# Energy_Sensor.net
KiCad netlist of a schematic drawn in EAGLE
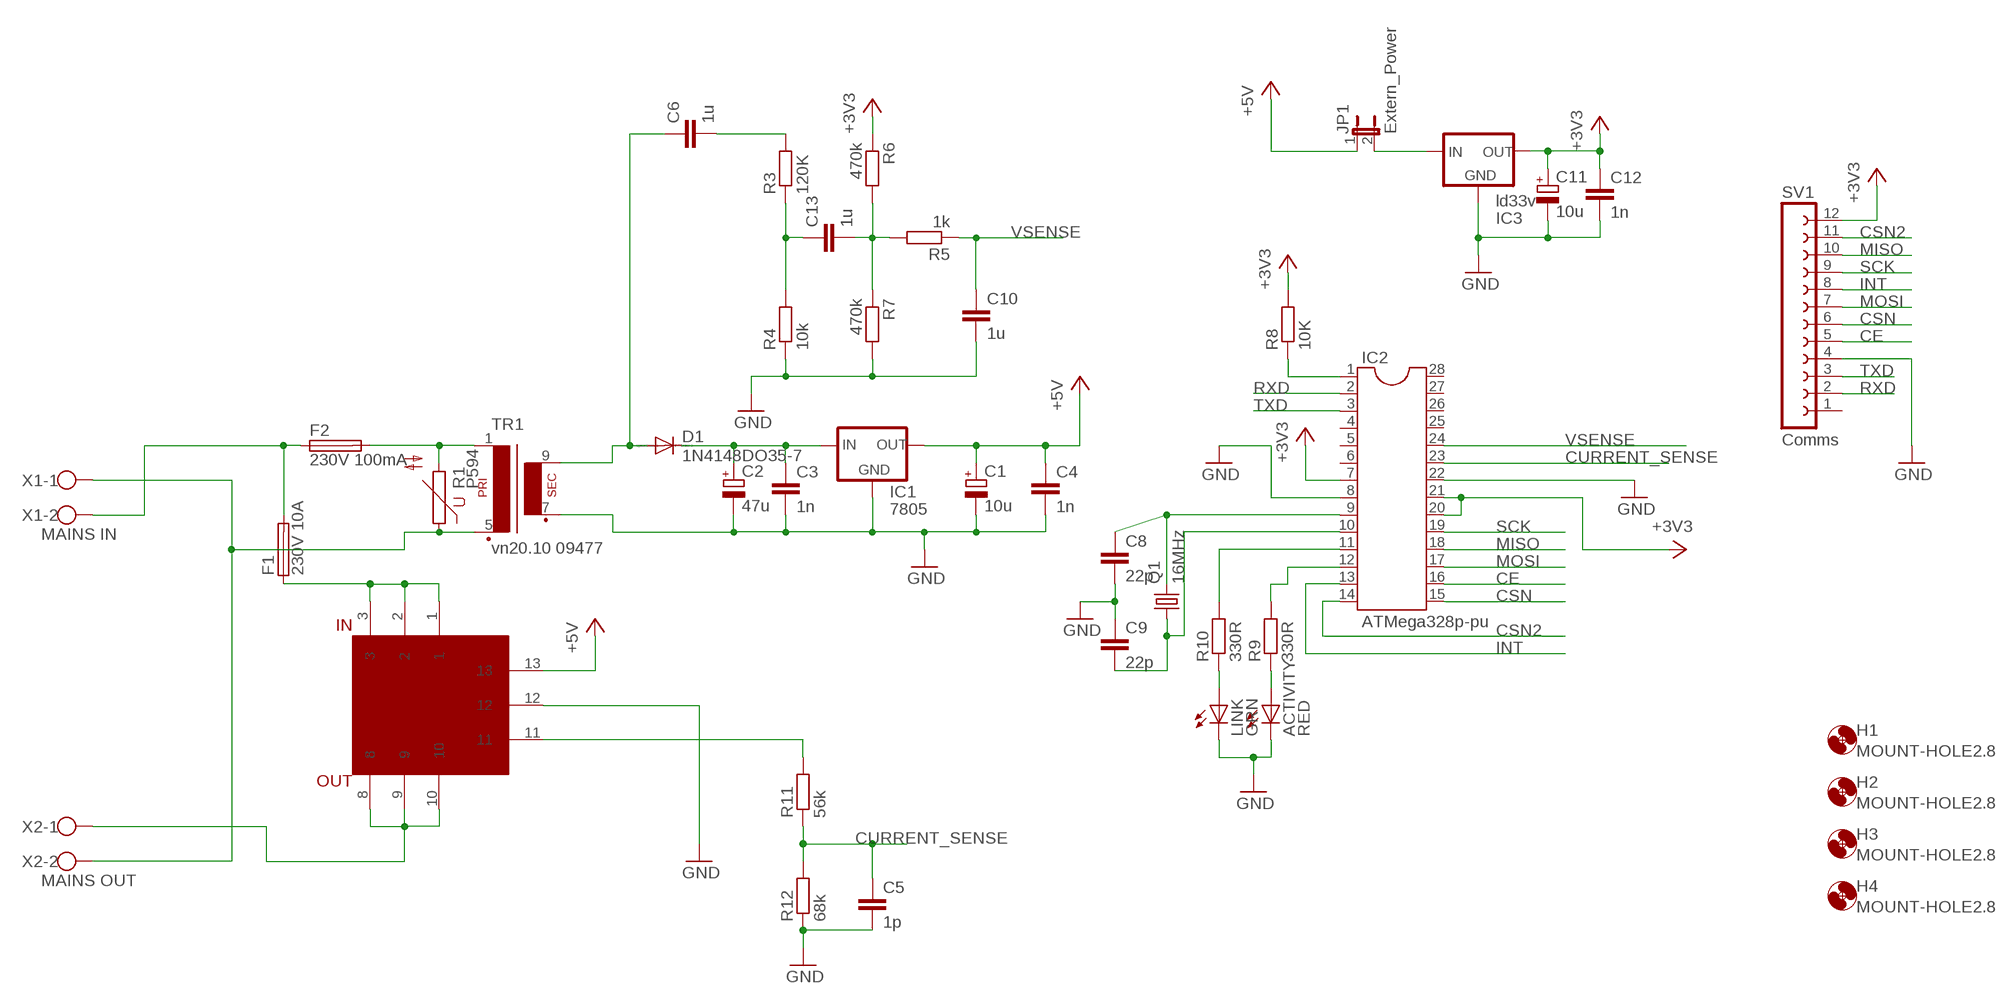
[diagram p0: schematic, sheet 1]

(export (version "E")
  (design (tool "Eeschema 10.0.6"))
  (components
    (comp (ref "ACTIVITY")
      (value "RED")
      (footprint "eagle-import:LED5MM")
      (libsource (lib "eagle-import") (part "LED5MM"))
    )
    (comp (ref "C1")
      (value "10u")
      (footprint "eagle-import:E2,5-6")
      (libsource (lib "eagle-import") (part "CPOL-EUE2.5-6"))
    )
    (comp (ref "C2")
      (value "47u")
      (footprint "eagle-import:E2,5-6")
      (libsource (lib "eagle-import") (part "CPOL-EUE2.5-6"))
    )
    (comp (ref "C3")
      (value "1n")
      (footprint "eagle-import:C025-025X050")
      (libsource (lib "eagle-import") (part "C-EU025-025X050"))
    )
    (comp (ref "C4")
      (value "1n")
      (footprint "eagle-import:C025-025X050")
      (libsource (lib "eagle-import") (part "C-EU025-025X050"))
    )
    (comp (ref "C5")
      (value "1p")
      (footprint "eagle-import:C025-025X050")
      (libsource (lib "eagle-import") (part "C-EU025-025X050"))
    )
    (comp (ref "C6")
      (value "1u")
      (footprint "eagle-import:C025-025X050")
      (libsource (lib "eagle-import") (part "C-EU025-025X050"))
    )
    (comp (ref "C8")
      (value "22p")
      (footprint "eagle-import:C025-025X050")
      (libsource (lib "eagle-import") (part "C-EU025-025X050"))
    )
    (comp (ref "C9")
      (value "22p")
      (footprint "eagle-import:C025-025X050")
      (libsource (lib "eagle-import") (part "C-EU025-025X050"))
    )
    (comp (ref "C10")
      (value "1u")
      (footprint "eagle-import:C025-025X050")
      (libsource (lib "eagle-import") (part "C-EU025-025X050"))
    )
    (comp (ref "C11")
      (value "10u")
      (footprint "eagle-import:E2,5-6")
      (libsource (lib "eagle-import") (part "CPOL-EUE2.5-6"))
    )
    (comp (ref "C12")
      (value "1n")
      (footprint "eagle-import:C025-025X050")
      (libsource (lib "eagle-import") (part "C-EU025-025X050"))
    )
    (comp (ref "C13")
      (value "1u")
      (footprint "eagle-import:C025-025X050")
      (libsource (lib "eagle-import") (part "C-EU025-025X050"))
    )
    (comp (ref "D1")
      (value "1N4148DO35-7")
      (footprint "eagle-import:DO35-7")
      (libsource (lib "eagle-import") (part "1N4148DO35-7"))
    )
    (comp (ref "F1")
      (value "230V 10A")
      (footprint "eagle-import:SH22,5A")
      (fields (field (name "MPN") "0031.7701.11"))
      (libsource (lib "eagle-import") (part "SH22,5A"))
    )
    (comp (ref "F2")
      (value "230V 100mA")
      (footprint "eagle-import:SH22,5A")
      (fields (field (name "MPN") "0031.7701.11"))
      (libsource (lib "eagle-import") (part "SH22,5A"))
    )
    (comp (ref "H1")
      (value "MOUNT-HOLE2.8")
      (footprint "eagle-import:2,8")
      (libsource (lib "eagle-import") (part "MOUNT-HOLE2.8"))
    )
    (comp (ref "H2")
      (value "MOUNT-HOLE2.8")
      (footprint "eagle-import:2,8")
      (libsource (lib "eagle-import") (part "MOUNT-HOLE2.8"))
    )
    (comp (ref "H3")
      (value "MOUNT-HOLE2.8")
      (footprint "eagle-import:2,8")
      (libsource (lib "eagle-import") (part "MOUNT-HOLE2.8"))
    )
    (comp (ref "H4")
      (value "MOUNT-HOLE2.8")
      (footprint "eagle-import:2,8")
      (libsource (lib "eagle-import") (part "MOUNT-HOLE2.8"))
    )
    (comp (ref "IC1")
      (value "7805")
      (footprint "eagle-import:78XXL")
      (libsource (lib "eagle-import") (part "78XXL"))
    )
    (comp (ref "IC2")
      (value "ATMega328p-pu")
      (footprint "eagle-import:DIL28-3")
      (libsource (lib "eagle-import") (part "DIL28-3"))
    )
    (comp (ref "IC3")
      (value "ld33v")
      (footprint "eagle-import:79XXL")
      (libsource (lib "eagle-import") (part "79XXL"))
    )
    (comp (ref "JP1")
      (value "Extern_Power")
      (footprint "eagle-import:JP1")
      (libsource (lib "eagle-import") (part "JP1E"))
    )
    (comp (ref "LINK")
      (value "GRN")
      (footprint "eagle-import:LED5MM")
      (libsource (lib "eagle-import") (part "LED5MM"))
    )
    (comp (ref "Q1")
      (value "16MHz")
      (footprint "eagle-import:HC49_S")
      (libsource (lib "eagle-import") (part "CRYSTALHC49S"))
    )
    (comp (ref "R1")
      (value "P594")
      (footprint "eagle-import:P594")
      (libsource (lib "eagle-import") (part "P594"))
    )
    (comp (ref "R3")
      (value "120K")
      (footprint "eagle-import:0207_7")
      (libsource (lib "eagle-import") (part "R-EU_0207/7"))
    )
    (comp (ref "R4")
      (value "10k")
      (footprint "eagle-import:0207_7")
      (libsource (lib "eagle-import") (part "R-EU_0207/7"))
    )
    (comp (ref "R5")
      (value "1k")
      (footprint "eagle-import:0207_7")
      (libsource (lib "eagle-import") (part "R-EU_0207/7"))
    )
    (comp (ref "R6")
      (value "470k")
      (footprint "eagle-import:0207_7")
      (libsource (lib "eagle-import") (part "R-EU_0207/7"))
    )
    (comp (ref "R7")
      (value "470k")
      (footprint "eagle-import:0207_7")
      (libsource (lib "eagle-import") (part "R-EU_0207/7"))
    )
    (comp (ref "R8")
      (value "10K")
      (footprint "eagle-import:0207_7")
      (libsource (lib "eagle-import") (part "R-EU_0207/7"))
    )
    (comp (ref "R9")
      (value "330R")
      (footprint "eagle-import:0207_7")
      (libsource (lib "eagle-import") (part "R-EU_0207/7"))
    )
    (comp (ref "R10")
      (value "330R")
      (footprint "eagle-import:0207_7")
      (libsource (lib "eagle-import") (part "R-EU_0207/7"))
    )
    (comp (ref "R11")
      (value "56k")
      (footprint "eagle-import:0207_7")
      (libsource (lib "eagle-import") (part "R-EU_0207/7"))
    )
    (comp (ref "R12")
      (value "68k")
      (footprint "eagle-import:0207_7")
      (libsource (lib "eagle-import") (part "R-EU_0207/7"))
    )
    (comp (ref "SV1")
      (value "Comms")
      (footprint "eagle-import:FE12W")
      (libsource (lib "eagle-import") (part "FE12W"))
    )
    (comp (ref "TR1")
      (value "vn20.10 09477")
      (footprint "eagle-import:VV11")
      (libsource (lib "eagle-import") (part "VV11"))
    )
    (comp (ref "U$1")
      (value "CAS25-NP")
      (footprint "eagle-import:CAS")
      (libsource (lib "eagle-import") (part "CAS25-NP"))
    )
    (comp (ref "X1")
      (value "MAINS IN")
      (footprint "eagle-import:W237-102")
      (fields (field (name "MPN") "237-102"))
      (libsource (lib "eagle-import") (part "W237-102"))
    )
    (comp (ref "X2")
      (value "MAINS OUT")
      (footprint "eagle-import:W237-102")
      (fields (field (name "MPN") "237-102"))
      (libsource (lib "eagle-import") (part "W237-102"))
    )
  )
  (nets
    (net (code "1") (name "+3V3") (class "Default")
      (node (ref "C11") (pin "+") (pinfunction "+_+") (pintype "passive"))
      (node (ref "C12") (pin "1") (pinfunction "1_1") (pintype "passive"))
      (node (ref "IC2") (pin "20") (pinfunction "20_20") (pintype "passive"))
      (node (ref "IC2") (pin "21") (pinfunction "21_21") (pintype "passive"))
      (node (ref "IC2") (pin "7") (pinfunction "7_7") (pintype "passive"))
      (node (ref "IC3") (pin "OUT") (pinfunction "OUT_OUT") (pintype "passive"))
      (node (ref "R6") (pin "1") (pinfunction "1_1") (pintype "passive"))
      (node (ref "R8") (pin "2") (pinfunction "2_2") (pintype "passive"))
      (node (ref "SV1") (pin "12") (pinfunction "12_12") (pintype "passive"))
    )
    (net (code "2") (name "+5V") (class "Default")
      (node (ref "C1") (pin "+") (pinfunction "+_+") (pintype "passive"))
      (node (ref "C4") (pin "1") (pinfunction "1_1") (pintype "passive"))
      (node (ref "IC1") (pin "OUT") (pinfunction "OUT_OUT") (pintype "passive"))
      (node (ref "JP1") (pin "1") (pinfunction "1_1") (pintype "passive"))
      (node (ref "U$1") (pin "13") (pinfunction "13_13") (pintype "bidirectional"))
    )
    (net (code "3") (name "/CE") (class "Default")
      (node (ref "IC2") (pin "16") (pinfunction "16_16") (pintype "passive"))
      (node (ref "SV1") (pin "5") (pinfunction "5_5") (pintype "passive"))
    )
    (net (code "4") (name "/CSN") (class "Default")
      (node (ref "IC2") (pin "15") (pinfunction "15_15") (pintype "passive"))
      (node (ref "SV1") (pin "6") (pinfunction "6_6") (pintype "passive"))
    )
    (net (code "5") (name "/CSN2") (class "Default")
      (node (ref "IC2") (pin "14") (pinfunction "14_14") (pintype "passive"))
      (node (ref "SV1") (pin "11") (pinfunction "11_11") (pintype "passive"))
    )
    (net (code "6") (name "/CURRENT_SENSE") (class "Default")
      (node (ref "C5") (pin "1") (pinfunction "1_1") (pintype "passive"))
      (node (ref "IC2") (pin "23") (pinfunction "23_23") (pintype "passive"))
      (node (ref "R11") (pin "1") (pinfunction "1_1") (pintype "passive"))
      (node (ref "R12") (pin "2") (pinfunction "2_2") (pintype "passive"))
    )
    (net (code "7") (name "/INT") (class "Default")
      (node (ref "IC2") (pin "13") (pinfunction "13_13") (pintype "passive"))
      (node (ref "SV1") (pin "8") (pinfunction "8_8") (pintype "passive"))
    )
    (net (code "8") (name "/MISO") (class "Default")
      (node (ref "IC2") (pin "18") (pinfunction "18_18") (pintype "passive"))
      (node (ref "SV1") (pin "10") (pinfunction "10_10") (pintype "passive"))
    )
    (net (code "9") (name "/MOSI") (class "Default")
      (node (ref "IC2") (pin "17") (pinfunction "17_17") (pintype "passive"))
      (node (ref "SV1") (pin "7") (pinfunction "7_7") (pintype "passive"))
    )
    (net (code "10") (name "/RXD") (class "Default")
      (node (ref "IC2") (pin "2") (pinfunction "2_2") (pintype "passive"))
      (node (ref "SV1") (pin "2") (pinfunction "2_2") (pintype "passive"))
    )
    (net (code "11") (name "/SCK") (class "Default")
      (node (ref "IC2") (pin "19") (pinfunction "19_19") (pintype "passive"))
      (node (ref "SV1") (pin "9") (pinfunction "9_9") (pintype "passive"))
    )
    (net (code "12") (name "/TXD") (class "Default")
      (node (ref "IC2") (pin "3") (pinfunction "3_3") (pintype "passive"))
      (node (ref "SV1") (pin "3") (pinfunction "3_3") (pintype "passive"))
    )
    (net (code "13") (name "/VSENSE") (class "Default")
      (node (ref "C10") (pin "1") (pinfunction "1_1") (pintype "passive"))
      (node (ref "IC2") (pin "24") (pinfunction "24_24") (pintype "passive"))
      (node (ref "R5") (pin "1") (pinfunction "1_1") (pintype "passive"))
    )
    (net (code "14") (name "GND") (class "Default")
      (node (ref "ACTIVITY") (pin "K") (pinfunction "C_K") (pintype "passive"))
      (node (ref "C1") (pin "-") (pinfunction "-_-") (pintype "passive"))
      (node (ref "C10") (pin "2") (pinfunction "2_2") (pintype "passive"))
      (node (ref "C11") (pin "-") (pinfunction "-_-") (pintype "passive"))
      (node (ref "C12") (pin "2") (pinfunction "2_2") (pintype "passive"))
      (node (ref "C2") (pin "-") (pinfunction "-_-") (pintype "passive"))
      (node (ref "C3") (pin "2") (pinfunction "2_2") (pintype "passive"))
      (node (ref "C4") (pin "2") (pinfunction "2_2") (pintype "passive"))
      (node (ref "C5") (pin "2") (pinfunction "2_2") (pintype "passive"))
      (node (ref "C8") (pin "2") (pinfunction "2_2") (pintype "passive"))
      (node (ref "C9") (pin "1") (pinfunction "1_1") (pintype "passive"))
      (node (ref "IC1") (pin "GND") (pinfunction "GND_GND") (pintype "input"))
      (node (ref "IC2") (pin "22") (pinfunction "22_22") (pintype "passive"))
      (node (ref "IC2") (pin "8") (pinfunction "8_8") (pintype "passive"))
      (node (ref "IC3") (pin "GND") (pinfunction "GND_GND") (pintype "input"))
      (node (ref "LINK") (pin "K") (pinfunction "C_K") (pintype "passive"))
      (node (ref "R12") (pin "1") (pinfunction "1_1") (pintype "passive"))
      (node (ref "R4") (pin "1") (pinfunction "1_1") (pintype "passive"))
      (node (ref "R7") (pin "2") (pinfunction "2_2") (pintype "passive"))
      (node (ref "SV1") (pin "4") (pinfunction "4_4") (pintype "passive"))
      (node (ref "TR1") (pin "7") (pinfunction "S3_7") (pintype "passive"))
      (node (ref "U$1") (pin "12") (pinfunction "12_12") (pintype "bidirectional"))
    )
    (net (code "15") (name "Net-(ACTIVITY-PadA)") (class "Default")
      (node (ref "ACTIVITY") (pin "A") (pinfunction "A_A") (pintype "passive"))
      (node (ref "R9") (pin "1") (pinfunction "1_1") (pintype "passive"))
    )
    (net (code "16") (name "Net-(C2-Pad+)") (class "Default")
      (node (ref "C2") (pin "+") (pinfunction "+_+") (pintype "passive"))
      (node (ref "C3") (pin "1") (pinfunction "1_1") (pintype "passive"))
      (node (ref "D1") (pin "C") (pinfunction "C_C") (pintype "passive"))
      (node (ref "IC1") (pin "IN") (pinfunction "IN_IN") (pintype "input"))
    )
    (net (code "17") (name "Net-(C6-Pad2)") (class "Default")
      (node (ref "C6") (pin "2") (pinfunction "2_2") (pintype "passive"))
      (node (ref "R3") (pin "2") (pinfunction "2_2") (pintype "passive"))
    )
    (net (code "18") (name "Net-(C8-Pad1)") (class "Default")
      (node (ref "C8") (pin "1") (pinfunction "1_1") (pintype "passive"))
      (node (ref "IC2") (pin "9") (pinfunction "9_9") (pintype "passive"))
      (node (ref "Q1") (pin "2") (pinfunction "2_2") (pintype "passive"))
    )
    (net (code "19") (name "Net-(C9-Pad2)") (class "Default")
      (node (ref "C9") (pin "2") (pinfunction "2_2") (pintype "passive"))
      (node (ref "IC2") (pin "10") (pinfunction "10_10") (pintype "passive"))
      (node (ref "Q1") (pin "1") (pinfunction "1_1") (pintype "passive"))
    )
    (net (code "20") (name "Net-(C13-Pad1)") (class "Default")
      (node (ref "C13") (pin "1") (pinfunction "1_1") (pintype "passive"))
      (node (ref "R3") (pin "1") (pinfunction "1_1") (pintype "passive"))
      (node (ref "R4") (pin "2") (pinfunction "2_2") (pintype "passive"))
    )
    (net (code "21") (name "Net-(C13-Pad2)") (class "Default")
      (node (ref "C13") (pin "2") (pinfunction "2_2") (pintype "passive"))
      (node (ref "R5") (pin "2") (pinfunction "2_2") (pintype "passive"))
      (node (ref "R6") (pin "2") (pinfunction "2_2") (pintype "passive"))
      (node (ref "R7") (pin "1") (pinfunction "1_1") (pintype "passive"))
    )
    (net (code "22") (name "Net-(F1-Pad1)") (class "Default")
      (node (ref "F1") (pin "1") (pinfunction "1_1") (pintype "passive"))
      (node (ref "U$1") (pin "1") (pinfunction "1_1") (pintype "bidirectional"))
      (node (ref "U$1") (pin "2") (pinfunction "2_2") (pintype "bidirectional"))
      (node (ref "U$1") (pin "3") (pinfunction "3_3") (pintype "bidirectional"))
    )
    (net (code "23") (name "Net-(IC2-Pad1)") (class "Default")
      (node (ref "IC2") (pin "1") (pinfunction "1_1") (pintype "passive"))
      (node (ref "R8") (pin "1") (pinfunction "1_1") (pintype "passive"))
    )
    (net (code "24") (name "Net-(IC2-Pad11)") (class "Default")
      (node (ref "IC2") (pin "11") (pinfunction "11_11") (pintype "passive"))
      (node (ref "R10") (pin "2") (pinfunction "2_2") (pintype "passive"))
    )
    (net (code "25") (name "Net-(IC2-Pad12)") (class "Default")
      (node (ref "IC2") (pin "12") (pinfunction "12_12") (pintype "passive"))
      (node (ref "R9") (pin "2") (pinfunction "2_2") (pintype "passive"))
    )
    (net (code "26") (name "Net-(IC3-PadIN)") (class "Default")
      (node (ref "IC3") (pin "IN") (pinfunction "IN_IN") (pintype "input"))
      (node (ref "JP1") (pin "2") (pinfunction "2_2") (pintype "passive"))
    )
    (net (code "27") (name "Net-(LINK-PadA)") (class "Default")
      (node (ref "LINK") (pin "A") (pinfunction "A_A") (pintype "passive"))
      (node (ref "R10") (pin "1") (pinfunction "1_1") (pintype "passive"))
    )
    (net (code "28") (name "Net-(R11-Pad2)") (class "Default")
      (node (ref "R11") (pin "2") (pinfunction "2_2") (pintype "passive"))
      (node (ref "U$1") (pin "11") (pinfunction "11_11") (pintype "bidirectional"))
    )
    (net (code "29") (name "Net-(TR1-P1)") (class "Default")
      (node (ref "F2") (pin "2") (pinfunction "2_2") (pintype "passive"))
      (node (ref "R1") (pin "2") (pinfunction "2_2") (pintype "passive"))
      (node (ref "TR1") (pin "1") (pinfunction "P1_1") (pintype "passive"))
    )
    (net (code "30") (name "Net-(TR1-P2)") (class "Default")
      (node (ref "R1") (pin "1") (pinfunction "1_1") (pintype "passive"))
      (node (ref "TR1") (pin "5") (pinfunction "P2_5") (pintype "passive"))
      (node (ref "X1") (pin "1") (pinfunction "KL_1") (pintype "passive"))
      (node (ref "X2") (pin "2") (pinfunction "KL_2") (pintype "passive"))
    )
    (net (code "31") (name "Net-(TR1-S4)") (class "Default")
      (node (ref "C6") (pin "1") (pinfunction "1_1") (pintype "passive"))
      (node (ref "D1") (pin "A") (pinfunction "A_A") (pintype "passive"))
      (node (ref "TR1") (pin "9") (pinfunction "S4_9") (pintype "passive"))
    )
    (net (code "32") (name "Net-(X1B-KL)") (class "Default")
      (node (ref "F1") (pin "2") (pinfunction "2_2") (pintype "passive"))
      (node (ref "F2") (pin "1") (pinfunction "1_1") (pintype "passive"))
      (node (ref "X1") (pin "2") (pinfunction "KL_2") (pintype "passive"))
    )
    (net (code "33") (name "Net-(X2A-KL)") (class "Default")
      (node (ref "U$1") (pin "10") (pinfunction "10_10") (pintype "bidirectional"))
      (node (ref "U$1") (pin "8") (pinfunction "8_8") (pintype "bidirectional"))
      (node (ref "U$1") (pin "9") (pinfunction "9_9") (pintype "bidirectional"))
      (node (ref "X2") (pin "1") (pinfunction "KL_1") (pintype "passive"))
    )
    (net (code "34") (name "unconnected-(IC2-Pad4)") (class "Default")
      (node (ref "IC2") (pin "4") (pinfunction "4_4") (pintype "passive"))
    )
    (net (code "35") (name "unconnected-(IC2-Pad5)") (class "Default")
      (node (ref "IC2") (pin "5") (pinfunction "5_5") (pintype "passive"))
    )
    (net (code "36") (name "unconnected-(IC2-Pad6)") (class "Default")
      (node (ref "IC2") (pin "6") (pinfunction "6_6") (pintype "passive"))
    )
    (net (code "37") (name "unconnected-(IC2-Pad25)") (class "Default")
      (node (ref "IC2") (pin "25") (pinfunction "25_25") (pintype "passive"))
    )
    (net (code "38") (name "unconnected-(IC2-Pad26)") (class "Default")
      (node (ref "IC2") (pin "26") (pinfunction "26_26") (pintype "passive"))
    )
    (net (code "39") (name "unconnected-(IC2-Pad27)") (class "Default")
      (node (ref "IC2") (pin "27") (pinfunction "27_27") (pintype "passive"))
    )
    (net (code "40") (name "unconnected-(IC2-Pad28)") (class "Default")
      (node (ref "IC2") (pin "28") (pinfunction "28_28") (pintype "passive"))
    )
    (net (code "41") (name "unconnected-(SV1-Pad1)") (class "Default")
      (node (ref "SV1") (pin "1") (pinfunction "1_1") (pintype "passive"))
    )
  )
)
